# M705D.net
KiCad netlist of a schematic drawn in EAGLE
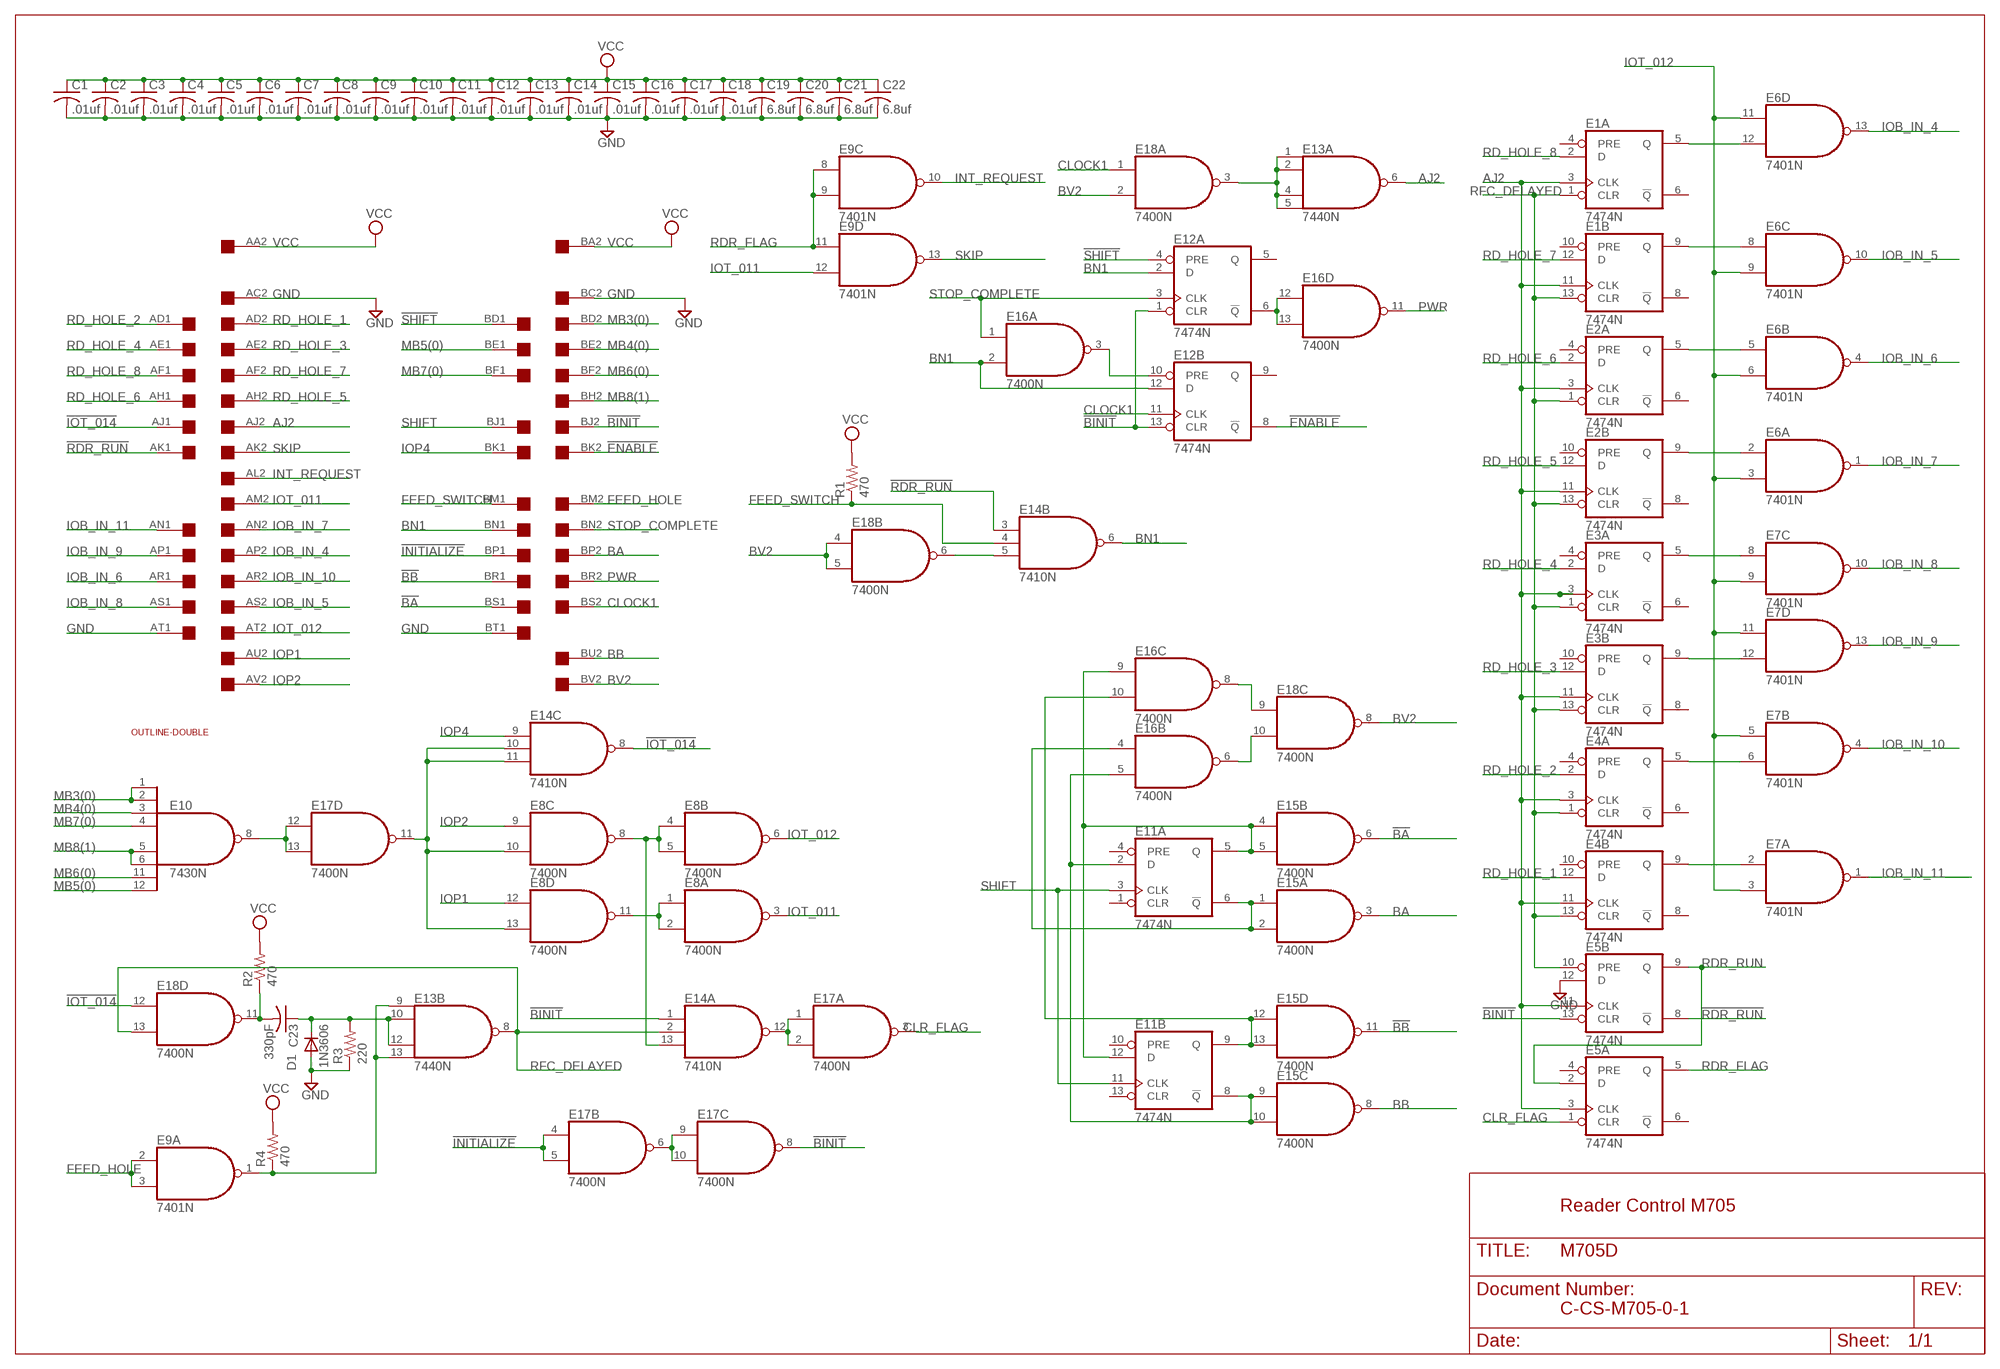
[diagram p0: schematic, sheet 1]

(export (version "E")
  (design (tool "Eeschema 10.0.6"))
  (components
    (comp (ref "C1")
      (value ".01uf")
      (footprint "eagle-import:C075-032X103")
      (libsource (lib "eagle-import") (part "C-US075-032X103"))
    )
    (comp (ref "C2")
      (value ".01uf")
      (footprint "eagle-import:C075-032X103")
      (libsource (lib "eagle-import") (part "C-US075-032X103"))
    )
    (comp (ref "C3")
      (value ".01uf")
      (footprint "eagle-import:C075-032X103")
      (libsource (lib "eagle-import") (part "C-US075-032X103"))
    )
    (comp (ref "C4")
      (value ".01uf")
      (footprint "eagle-import:C075-032X103")
      (libsource (lib "eagle-import") (part "C-US075-032X103"))
    )
    (comp (ref "C5")
      (value ".01uf")
      (footprint "eagle-import:C075-032X103")
      (libsource (lib "eagle-import") (part "C-US075-032X103"))
    )
    (comp (ref "C6")
      (value ".01uf")
      (footprint "eagle-import:C075-032X103")
      (libsource (lib "eagle-import") (part "C-US075-032X103"))
    )
    (comp (ref "C7")
      (value ".01uf")
      (footprint "eagle-import:C075-032X103")
      (libsource (lib "eagle-import") (part "C-US075-032X103"))
    )
    (comp (ref "C8")
      (value ".01uf")
      (footprint "eagle-import:C075-032X103")
      (libsource (lib "eagle-import") (part "C-US075-032X103"))
    )
    (comp (ref "C9")
      (value ".01uf")
      (footprint "eagle-import:C075-032X103")
      (libsource (lib "eagle-import") (part "C-US075-032X103"))
    )
    (comp (ref "C10")
      (value ".01uf")
      (footprint "eagle-import:C075-032X103")
      (libsource (lib "eagle-import") (part "C-US075-032X103"))
    )
    (comp (ref "C11")
      (value ".01uf")
      (footprint "eagle-import:C075-032X103")
      (libsource (lib "eagle-import") (part "C-US075-032X103"))
    )
    (comp (ref "C12")
      (value ".01uf")
      (footprint "eagle-import:C075-032X103")
      (libsource (lib "eagle-import") (part "C-US075-032X103"))
    )
    (comp (ref "C13")
      (value ".01uf")
      (footprint "eagle-import:C075-032X103")
      (libsource (lib "eagle-import") (part "C-US075-032X103"))
    )
    (comp (ref "C14")
      (value ".01uf")
      (footprint "eagle-import:C075-032X103")
      (libsource (lib "eagle-import") (part "C-US075-032X103"))
    )
    (comp (ref "C15")
      (value ".01uf")
      (footprint "eagle-import:C075-032X103")
      (libsource (lib "eagle-import") (part "C-US075-032X103"))
    )
    (comp (ref "C16")
      (value ".01uf")
      (footprint "eagle-import:C075-032X103")
      (libsource (lib "eagle-import") (part "C-US075-032X103"))
    )
    (comp (ref "C17")
      (value ".01uf")
      (footprint "eagle-import:C075-032X103")
      (libsource (lib "eagle-import") (part "C-US075-032X103"))
    )
    (comp (ref "C18")
      (value ".01uf")
      (footprint "eagle-import:C075-032X103")
      (libsource (lib "eagle-import") (part "C-US075-032X103"))
    )
    (comp (ref "C19")
      (value "6.8uf")
      (footprint "eagle-import:C150-054X183")
      (libsource (lib "eagle-import") (part "C-US150-054X183"))
    )
    (comp (ref "C20")
      (value "6.8uf")
      (footprint "eagle-import:C150-054X183")
      (libsource (lib "eagle-import") (part "C-US150-054X183"))
    )
    (comp (ref "C21")
      (value "6.8uf")
      (footprint "eagle-import:C150-054X183")
      (libsource (lib "eagle-import") (part "C-US150-054X183"))
    )
    (comp (ref "C22")
      (value "6.8uf")
      (footprint "eagle-import:C150-054X183")
      (libsource (lib "eagle-import") (part "C-US150-054X183"))
    )
    (comp (ref "C23")
      (value "330pF")
      (footprint "eagle-import:C075-032X103")
      (libsource (lib "eagle-import") (part "C-US075-032X103"))
    )
    (comp (ref "D1")
      (value "1N3606")
      (footprint "eagle-import:DO35-10")
      (libsource (lib "eagle-import") (part "1N4148DO35-10"))
    )
    (comp (ref "E1")
      (value "7474N")
      (footprint "eagle-import:DIL14")
      (libsource (lib "eagle-import") (part "7474NS"))
    )
    (comp (ref "E2")
      (value "7474N")
      (footprint "eagle-import:DIL14")
      (libsource (lib "eagle-import") (part "7474NS"))
    )
    (comp (ref "E3")
      (value "7474N")
      (footprint "eagle-import:DIL14")
      (libsource (lib "eagle-import") (part "7474NS"))
    )
    (comp (ref "E4")
      (value "7474N")
      (footprint "eagle-import:DIL14")
      (libsource (lib "eagle-import") (part "7474NS"))
    )
    (comp (ref "E5")
      (value "7474N")
      (footprint "eagle-import:DIL14")
      (libsource (lib "eagle-import") (part "7474NS"))
    )
    (comp (ref "E6")
      (value "7401N")
      (footprint "eagle-import:DIL14")
      (libsource (lib "eagle-import") (part "7401NLS"))
    )
    (comp (ref "E7")
      (value "7401N")
      (footprint "eagle-import:DIL14")
      (libsource (lib "eagle-import") (part "7401NLS"))
    )
    (comp (ref "E8")
      (value "7400N")
      (footprint "eagle-import:DIL14")
      (libsource (lib "eagle-import") (part "7400N"))
    )
    (comp (ref "E9")
      (value "7401N")
      (footprint "eagle-import:DIL14")
      (libsource (lib "eagle-import") (part "7401NLS"))
    )
    (comp (ref "E10")
      (value "7430N")
      (footprint "eagle-import:DIL14")
      (libsource (lib "eagle-import") (part "7430N"))
    )
    (comp (ref "E11")
      (value "7474N")
      (footprint "eagle-import:DIL14")
      (libsource (lib "eagle-import") (part "7474NS"))
    )
    (comp (ref "E12")
      (value "7474N")
      (footprint "eagle-import:DIL14")
      (libsource (lib "eagle-import") (part "7474NS"))
    )
    (comp (ref "E13")
      (value "7440N")
      (footprint "eagle-import:DIL14")
      (libsource (lib "eagle-import") (part "7420NS"))
    )
    (comp (ref "E14")
      (value "7410N")
      (footprint "eagle-import:DIL14")
      (libsource (lib "eagle-import") (part "7410N"))
    )
    (comp (ref "E15")
      (value "7400N")
      (footprint "eagle-import:DIL14")
      (libsource (lib "eagle-import") (part "7400N"))
    )
    (comp (ref "E16")
      (value "7400N")
      (footprint "eagle-import:DIL14")
      (libsource (lib "eagle-import") (part "7400N"))
    )
    (comp (ref "E17")
      (value "7400N")
      (footprint "eagle-import:DIL14")
      (libsource (lib "eagle-import") (part "7400N"))
    )
    (comp (ref "E18")
      (value "7400N")
      (footprint "eagle-import:DIL14")
      (libsource (lib "eagle-import") (part "7400N"))
    )
    (comp (ref "R1")
      (value "470")
      (footprint "eagle-import:0207_10")
      (libsource (lib "eagle-import") (part "R-US_0207/10"))
    )
    (comp (ref "R2")
      (value "470")
      (footprint "eagle-import:0207_10")
      (libsource (lib "eagle-import") (part "R-US_0207/10"))
    )
    (comp (ref "R3")
      (value "220")
      (footprint "eagle-import:0207_10")
      (libsource (lib "eagle-import") (part "R-US_0207/10"))
    )
    (comp (ref "R4")
      (value "470")
      (footprint "eagle-import:0207_10")
      (libsource (lib "eagle-import") (part "R-US_0207/10"))
    )
    (comp (ref "U$5")
      (value "DOUBLE")
      (footprint "eagle-import:EDGE-CON4")
      (libsource (lib "eagle-import") (part "DOUBLE"))
    )
    (comp (ref "U$6")
      (value "OUTLINE-DOUBLE")
      (footprint "eagle-import:DOUBLE")
      (libsource (lib "eagle-import") (part "OUTLINE-DOUBLE"))
    )
  )
  (nets
    (net (code "1") (name "/AJ2") (class "Default")
      (node (ref "E1") (pin "11") (pinfunction "CLK_11") (pintype "input"))
      (node (ref "E1") (pin "3") (pinfunction "CLK_3") (pintype "input"))
      (node (ref "E13") (pin "6") (pinfunction "O_6") (pintype "output"))
      (node (ref "E2") (pin "11") (pinfunction "CLK_11") (pintype "input"))
      (node (ref "E2") (pin "3") (pinfunction "CLK_3") (pintype "input"))
      (node (ref "E3") (pin "11") (pinfunction "CLK_11") (pintype "input"))
      (node (ref "E3") (pin "3") (pinfunction "CLK_3") (pintype "input"))
      (node (ref "E4") (pin "11") (pinfunction "CLK_11") (pintype "input"))
      (node (ref "E4") (pin "3") (pinfunction "CLK_3") (pintype "input"))
      (node (ref "E5") (pin "11") (pinfunction "CLK_11") (pintype "input"))
      (node (ref "E5") (pin "3") (pinfunction "CLK_3") (pintype "input"))
      (node (ref "U$5") (pin "AJ2") (pinfunction "1_AJ2") (pintype "bidirectional"))
    )
    (net (code "2") (name "/BA") (class "Default")
      (node (ref "E15") (pin "3") (pinfunction "O_3") (pintype "output"))
      (node (ref "U$5") (pin "BP2") (pinfunction "1_BP2") (pintype "bidirectional"))
    )
    (net (code "3") (name "/BB") (class "Default")
      (node (ref "E15") (pin "8") (pinfunction "O_8") (pintype "output"))
      (node (ref "U$5") (pin "BU2") (pinfunction "1_BU2") (pintype "bidirectional"))
    )
    (net (code "4") (name "/BN1") (class "Default")
      (node (ref "E12") (pin "12") (pinfunction "D_12") (pintype "input"))
      (node (ref "E12") (pin "2") (pinfunction "D_2") (pintype "input"))
      (node (ref "E14") (pin "6") (pinfunction "O_6") (pintype "output"))
      (node (ref "E16") (pin "2") (pinfunction "I1_2") (pintype "input"))
      (node (ref "U$5") (pin "BN1") (pinfunction "1_BN1") (pintype "bidirectional"))
    )
    (net (code "5") (name "/BV2") (class "Default")
      (node (ref "E18") (pin "2") (pinfunction "I1_2") (pintype "input"))
      (node (ref "E18") (pin "4") (pinfunction "I0_4") (pintype "input"))
      (node (ref "E18") (pin "5") (pinfunction "I1_5") (pintype "input"))
      (node (ref "E18") (pin "8") (pinfunction "O_8") (pintype "output"))
      (node (ref "U$5") (pin "BV2") (pinfunction "1_BV2") (pintype "bidirectional"))
    )
    (net (code "6") (name "/CLOCK1") (class "Default")
      (node (ref "E12") (pin "11") (pinfunction "CLK_11") (pintype "input"))
      (node (ref "E18") (pin "1") (pinfunction "I0_1") (pintype "input"))
      (node (ref "U$5") (pin "BS2") (pinfunction "1_BS2") (pintype "bidirectional"))
    )
    (net (code "7") (name "/CLR_FLAG") (class "Default")
      (node (ref "E17") (pin "3") (pinfunction "O_3") (pintype "output"))
      (node (ref "E5") (pin "1") (pinfunction "CLR_1") (pintype "input"))
    )
    (net (code "8") (name "/FEED_HOLE") (class "Default")
      (node (ref "E9") (pin "2") (pinfunction "I0_2") (pintype "input"))
      (node (ref "E9") (pin "3") (pinfunction "I1_3") (pintype "input"))
      (node (ref "U$5") (pin "BM2") (pinfunction "1_BM2") (pintype "bidirectional"))
    )
    (net (code "9") (name "/FEED_SWITCH") (class "Default")
      (node (ref "E14") (pin "4") (pinfunction "I1_4") (pintype "input"))
      (node (ref "R1") (pin "1") (pinfunction "1_1") (pintype "passive"))
      (node (ref "U$5") (pin "BM1") (pinfunction "1_BM1") (pintype "bidirectional"))
    )
    (net (code "10") (name "/INT_REQUEST") (class "Default")
      (node (ref "E9") (pin "10") (pinfunction "O_10") (pintype "open_collector"))
      (node (ref "U$5") (pin "AL2") (pinfunction "1_AL2") (pintype "bidirectional"))
    )
    (net (code "11") (name "/IOB_IN_4") (class "Default")
      (node (ref "E6") (pin "13") (pinfunction "O_13") (pintype "open_collector"))
      (node (ref "U$5") (pin "AP2") (pinfunction "1_AP2") (pintype "bidirectional"))
    )
    (net (code "12") (name "/IOB_IN_5") (class "Default")
      (node (ref "E6") (pin "10") (pinfunction "O_10") (pintype "open_collector"))
      (node (ref "U$5") (pin "AS2") (pinfunction "1_AS2") (pintype "bidirectional"))
    )
    (net (code "13") (name "/IOB_IN_6") (class "Default")
      (node (ref "E6") (pin "4") (pinfunction "O_4") (pintype "open_collector"))
      (node (ref "U$5") (pin "AR1") (pinfunction "1_AR1") (pintype "bidirectional"))
    )
    (net (code "14") (name "/IOB_IN_7") (class "Default")
      (node (ref "E6") (pin "1") (pinfunction "O_1") (pintype "open_collector"))
      (node (ref "U$5") (pin "AN2") (pinfunction "1_AN2") (pintype "bidirectional"))
    )
    (net (code "15") (name "/IOB_IN_8") (class "Default")
      (node (ref "E7") (pin "10") (pinfunction "O_10") (pintype "open_collector"))
      (node (ref "U$5") (pin "AS1") (pinfunction "1_AS1") (pintype "bidirectional"))
    )
    (net (code "16") (name "/IOB_IN_9") (class "Default")
      (node (ref "E7") (pin "13") (pinfunction "O_13") (pintype "open_collector"))
      (node (ref "U$5") (pin "AP1") (pinfunction "1_AP1") (pintype "bidirectional"))
    )
    (net (code "17") (name "/IOB_IN_10") (class "Default")
      (node (ref "E7") (pin "4") (pinfunction "O_4") (pintype "open_collector"))
      (node (ref "U$5") (pin "AR2") (pinfunction "1_AR2") (pintype "bidirectional"))
    )
    (net (code "18") (name "/IOB_IN_11") (class "Default")
      (node (ref "E7") (pin "1") (pinfunction "O_1") (pintype "open_collector"))
      (node (ref "U$5") (pin "AN1") (pinfunction "1_AN1") (pintype "bidirectional"))
    )
    (net (code "19") (name "/IOP1") (class "Default")
      (node (ref "E8") (pin "12") (pinfunction "I0_12") (pintype "input"))
      (node (ref "U$5") (pin "AU2") (pinfunction "1_AU2") (pintype "bidirectional"))
    )
    (net (code "20") (name "/IOP2") (class "Default")
      (node (ref "E8") (pin "9") (pinfunction "I0_9") (pintype "input"))
      (node (ref "U$5") (pin "AV2") (pinfunction "1_AV2") (pintype "bidirectional"))
    )
    (net (code "21") (name "/IOP4") (class "Default")
      (node (ref "E14") (pin "9") (pinfunction "I0_9") (pintype "input"))
      (node (ref "U$5") (pin "BK1") (pinfunction "1_BK1") (pintype "bidirectional"))
    )
    (net (code "22") (name "/IOT_011") (class "Default")
      (node (ref "E8") (pin "3") (pinfunction "O_3") (pintype "output"))
      (node (ref "E9") (pin "12") (pinfunction "I1_12") (pintype "input"))
      (node (ref "U$5") (pin "AM2") (pinfunction "1_AM2") (pintype "bidirectional"))
    )
    (net (code "23") (name "/IOT_012") (class "Default")
      (node (ref "E6") (pin "11") (pinfunction "I0_11") (pintype "input"))
      (node (ref "E6") (pin "3") (pinfunction "I1_3") (pintype "input"))
      (node (ref "E6") (pin "6") (pinfunction "I1_6") (pintype "input"))
      (node (ref "E6") (pin "9") (pinfunction "I1_9") (pintype "input"))
      (node (ref "E7") (pin "11") (pinfunction "I0_11") (pintype "input"))
      (node (ref "E7") (pin "3") (pinfunction "I1_3") (pintype "input"))
      (node (ref "E7") (pin "5") (pinfunction "I0_5") (pintype "input"))
      (node (ref "E7") (pin "9") (pinfunction "I1_9") (pintype "input"))
      (node (ref "E8") (pin "6") (pinfunction "O_6") (pintype "output"))
      (node (ref "U$5") (pin "AT2") (pinfunction "1_AT2") (pintype "bidirectional"))
    )
    (net (code "24") (name "/MB3(0)") (class "Default")
      (node (ref "E10") (pin "1") (pinfunction "I0_1") (pintype "input"))
      (node (ref "E10") (pin "2") (pinfunction "I1_2") (pintype "input"))
      (node (ref "U$5") (pin "BD2") (pinfunction "1_BD2") (pintype "bidirectional"))
    )
    (net (code "25") (name "/MB4(0)") (class "Default")
      (node (ref "E10") (pin "3") (pinfunction "I2_3") (pintype "input"))
      (node (ref "U$5") (pin "BE2") (pinfunction "1_BE2") (pintype "bidirectional"))
    )
    (net (code "26") (name "/MB5(0)") (class "Default")
      (node (ref "E10") (pin "12") (pinfunction "I7_12") (pintype "input"))
      (node (ref "U$5") (pin "BE1") (pinfunction "1_BE1") (pintype "bidirectional"))
    )
    (net (code "27") (name "/MB6(0)") (class "Default")
      (node (ref "E10") (pin "11") (pinfunction "I6_11") (pintype "input"))
      (node (ref "U$5") (pin "BF2") (pinfunction "1_BF2") (pintype "bidirectional"))
    )
    (net (code "28") (name "/MB7(0)") (class "Default")
      (node (ref "E10") (pin "4") (pinfunction "I3_4") (pintype "input"))
      (node (ref "U$5") (pin "BF1") (pinfunction "1_BF1") (pintype "bidirectional"))
    )
    (net (code "29") (name "/MB8(1)") (class "Default")
      (node (ref "E10") (pin "5") (pinfunction "I4_5") (pintype "input"))
      (node (ref "E10") (pin "6") (pinfunction "I5_6") (pintype "input"))
      (node (ref "U$5") (pin "BH2") (pinfunction "1_BH2") (pintype "bidirectional"))
    )
    (net (code "30") (name "/PWR") (class "Default")
      (node (ref "E16") (pin "11") (pinfunction "O_11") (pintype "output"))
      (node (ref "U$5") (pin "BR2") (pinfunction "1_BR2") (pintype "bidirectional"))
    )
    (net (code "31") (name "/RDR_FLAG") (class "Default")
      (node (ref "E5") (pin "5") (pinfunction "Q_5") (pintype "output"))
      (node (ref "E9") (pin "11") (pinfunction "I0_11") (pintype "input"))
      (node (ref "E9") (pin "8") (pinfunction "I0_8") (pintype "input"))
      (node (ref "E9") (pin "9") (pinfunction "I1_9") (pintype "input"))
    )
    (net (code "32") (name "/RDR_RUN") (class "Default")
      (node (ref "E5") (pin "2") (pinfunction "D_2") (pintype "input"))
      (node (ref "E5") (pin "9") (pinfunction "Q_9") (pintype "output"))
    )
    (net (code "33") (name "/RD_HOLE_1") (class "Default")
      (node (ref "E4") (pin "12") (pinfunction "D_12") (pintype "input"))
      (node (ref "U$5") (pin "AD2") (pinfunction "1_AD2") (pintype "bidirectional"))
    )
    (net (code "34") (name "/RD_HOLE_2") (class "Default")
      (node (ref "E4") (pin "2") (pinfunction "D_2") (pintype "input"))
      (node (ref "U$5") (pin "AD1") (pinfunction "1_AD1") (pintype "bidirectional"))
    )
    (net (code "35") (name "/RD_HOLE_3") (class "Default")
      (node (ref "E3") (pin "12") (pinfunction "D_12") (pintype "input"))
      (node (ref "U$5") (pin "AE2") (pinfunction "1_AE2") (pintype "bidirectional"))
    )
    (net (code "36") (name "/RD_HOLE_4") (class "Default")
      (node (ref "E3") (pin "2") (pinfunction "D_2") (pintype "input"))
      (node (ref "U$5") (pin "AE1") (pinfunction "1_AE1") (pintype "bidirectional"))
    )
    (net (code "37") (name "/RD_HOLE_5") (class "Default")
      (node (ref "E2") (pin "12") (pinfunction "D_12") (pintype "input"))
      (node (ref "U$5") (pin "AH2") (pinfunction "1_AH2") (pintype "bidirectional"))
    )
    (net (code "38") (name "/RD_HOLE_6") (class "Default")
      (node (ref "E2") (pin "2") (pinfunction "D_2") (pintype "input"))
      (node (ref "U$5") (pin "AH1") (pinfunction "1_AH1") (pintype "bidirectional"))
    )
    (net (code "39") (name "/RD_HOLE_7") (class "Default")
      (node (ref "E1") (pin "12") (pinfunction "D_12") (pintype "input"))
      (node (ref "U$5") (pin "AF2") (pinfunction "1_AF2") (pintype "bidirectional"))
    )
    (net (code "40") (name "/RD_HOLE_8") (class "Default")
      (node (ref "E1") (pin "2") (pinfunction "D_2") (pintype "input"))
      (node (ref "U$5") (pin "AF1") (pinfunction "1_AF1") (pintype "bidirectional"))
    )
    (net (code "41") (name "/RFC_DELAYED") (class "Default")
      (node (ref "E1") (pin "1") (pinfunction "CLR_1") (pintype "input"))
      (node (ref "E1") (pin "13") (pinfunction "CLR_13") (pintype "input"))
      (node (ref "E13") (pin "8") (pinfunction "O_8") (pintype "output"))
      (node (ref "E14") (pin "2") (pinfunction "I1_2") (pintype "input"))
      (node (ref "E18") (pin "13") (pinfunction "I1_13") (pintype "input"))
      (node (ref "E2") (pin "1") (pinfunction "CLR_1") (pintype "input"))
      (node (ref "E2") (pin "13") (pinfunction "CLR_13") (pintype "input"))
      (node (ref "E3") (pin "1") (pinfunction "CLR_1") (pintype "input"))
      (node (ref "E3") (pin "13") (pinfunction "CLR_13") (pintype "input"))
      (node (ref "E4") (pin "1") (pinfunction "CLR_1") (pintype "input"))
      (node (ref "E4") (pin "13") (pinfunction "CLR_13") (pintype "input"))
      (node (ref "E5") (pin "10") (pinfunction "PRE_10") (pintype "input"))
    )
    (net (code "42") (name "/SHIFT") (class "Default")
      (node (ref "E11") (pin "11") (pinfunction "CLK_11") (pintype "input"))
      (node (ref "E11") (pin "3") (pinfunction "CLK_3") (pintype "input"))
      (node (ref "U$5") (pin "BJ1") (pinfunction "1_BJ1") (pintype "bidirectional"))
    )
    (net (code "43") (name "/SKIP") (class "Default")
      (node (ref "E9") (pin "13") (pinfunction "O_13") (pintype "open_collector"))
      (node (ref "U$5") (pin "AK2") (pinfunction "1_AK2") (pintype "bidirectional"))
    )
    (net (code "44") (name "/STOP_COMPLETE") (class "Default")
      (node (ref "E12") (pin "3") (pinfunction "CLK_3") (pintype "input"))
      (node (ref "E16") (pin "1") (pinfunction "I0_1") (pintype "input"))
      (node (ref "U$5") (pin "BN2") (pinfunction "1_BN2") (pintype "bidirectional"))
    )
    (net (code "45") (name "/~{BA}") (class "Default")
      (node (ref "E15") (pin "6") (pinfunction "O_6") (pintype "output"))
      (node (ref "U$5") (pin "BS1") (pinfunction "1_BS1") (pintype "bidirectional"))
    )
    (net (code "46") (name "/~{BB}") (class "Default")
      (node (ref "E15") (pin "11") (pinfunction "O_11") (pintype "output"))
      (node (ref "U$5") (pin "BR1") (pinfunction "1_BR1") (pintype "bidirectional"))
    )
    (net (code "47") (name "/~{BINIT}") (class "Default")
      (node (ref "E12") (pin "1") (pinfunction "CLR_1") (pintype "input"))
      (node (ref "E12") (pin "13") (pinfunction "CLR_13") (pintype "input"))
      (node (ref "E14") (pin "1") (pinfunction "I0_1") (pintype "input"))
      (node (ref "E17") (pin "8") (pinfunction "O_8") (pintype "output"))
      (node (ref "E5") (pin "13") (pinfunction "CLR_13") (pintype "input"))
      (node (ref "U$5") (pin "BJ2") (pinfunction "1_BJ2") (pintype "bidirectional"))
    )
    (net (code "48") (name "/~{ENABLE}") (class "Default")
      (node (ref "E12") (pin "8") (pinfunction "~{Q}_8") (pintype "output"))
      (node (ref "U$5") (pin "BK2") (pinfunction "1_BK2") (pintype "bidirectional"))
    )
    (net (code "49") (name "/~{INITIALIZE}") (class "Default")
      (node (ref "E17") (pin "4") (pinfunction "I0_4") (pintype "input"))
      (node (ref "E17") (pin "5") (pinfunction "I1_5") (pintype "input"))
      (node (ref "U$5") (pin "BP1") (pinfunction "1_BP1") (pintype "bidirectional"))
    )
    (net (code "50") (name "/~{IOT_014}") (class "Default")
      (node (ref "E14") (pin "8") (pinfunction "O_8") (pintype "output"))
      (node (ref "E18") (pin "12") (pinfunction "I0_12") (pintype "input"))
      (node (ref "U$5") (pin "AJ1") (pinfunction "1_AJ1") (pintype "bidirectional"))
    )
    (net (code "51") (name "/~{RDR_RUN}") (class "Default")
      (node (ref "E14") (pin "3") (pinfunction "I0_3") (pintype "input"))
      (node (ref "E5") (pin "8") (pinfunction "~{Q}_8") (pintype "output"))
      (node (ref "U$5") (pin "AK1") (pinfunction "1_AK1") (pintype "bidirectional"))
    )
    (net (code "52") (name "/~{SHIFT}") (class "Default")
      (node (ref "E12") (pin "4") (pinfunction "PRE_4") (pintype "input"))
      (node (ref "U$5") (pin "BD1") (pinfunction "1_BD1") (pintype "bidirectional"))
    )
    (net (code "53") (name "GND") (class "Default")
      (node (ref "C1") (pin "2") (pinfunction "2_2") (pintype "passive"))
      (node (ref "C10") (pin "2") (pinfunction "2_2") (pintype "passive"))
      (node (ref "C11") (pin "2") (pinfunction "2_2") (pintype "passive"))
      (node (ref "C12") (pin "2") (pinfunction "2_2") (pintype "passive"))
      (node (ref "C13") (pin "2") (pinfunction "2_2") (pintype "passive"))
      (node (ref "C14") (pin "2") (pinfunction "2_2") (pintype "passive"))
      (node (ref "C15") (pin "2") (pinfunction "2_2") (pintype "passive"))
      (node (ref "C16") (pin "2") (pinfunction "2_2") (pintype "passive"))
      (node (ref "C17") (pin "2") (pinfunction "2_2") (pintype "passive"))
      (node (ref "C18") (pin "2") (pinfunction "2_2") (pintype "passive"))
      (node (ref "C19") (pin "2") (pinfunction "2_2") (pintype "passive"))
      (node (ref "C2") (pin "2") (pinfunction "2_2") (pintype "passive"))
      (node (ref "C20") (pin "2") (pinfunction "2_2") (pintype "passive"))
      (node (ref "C21") (pin "2") (pinfunction "2_2") (pintype "passive"))
      (node (ref "C22") (pin "2") (pinfunction "2_2") (pintype "passive"))
      (node (ref "C3") (pin "2") (pinfunction "2_2") (pintype "passive"))
      (node (ref "C4") (pin "2") (pinfunction "2_2") (pintype "passive"))
      (node (ref "C5") (pin "2") (pinfunction "2_2") (pintype "passive"))
      (node (ref "C6") (pin "2") (pinfunction "2_2") (pintype "passive"))
      (node (ref "C7") (pin "2") (pinfunction "2_2") (pintype "passive"))
      (node (ref "C8") (pin "2") (pinfunction "2_2") (pintype "passive"))
      (node (ref "C9") (pin "2") (pinfunction "2_2") (pintype "passive"))
      (node (ref "D1") (pin "A") (pinfunction "A_A") (pintype "passive"))
      (node (ref "E5") (pin "12") (pinfunction "D_12") (pintype "input"))
      (node (ref "R3") (pin "1") (pinfunction "1_1") (pintype "passive"))
      (node (ref "U$5") (pin "AC2") (pinfunction "1_AC2") (pintype "bidirectional"))
      (node (ref "U$5") (pin "AT1") (pinfunction "1_AT1") (pintype "bidirectional"))
      (node (ref "U$5") (pin "BC2") (pinfunction "1_BC2") (pintype "bidirectional"))
      (node (ref "U$5") (pin "BT1") (pinfunction "1_BT1") (pintype "bidirectional"))
    )
    (net (code "54") (name "Net-(E1A-Q)") (class "Default")
      (node (ref "E1") (pin "5") (pinfunction "Q_5") (pintype "output"))
      (node (ref "E6") (pin "12") (pinfunction "I1_12") (pintype "input"))
    )
    (net (code "55") (name "Net-(E1B-Q)") (class "Default")
      (node (ref "E1") (pin "9") (pinfunction "Q_9") (pintype "output"))
      (node (ref "E6") (pin "8") (pinfunction "I0_8") (pintype "input"))
    )
    (net (code "56") (name "Net-(E2A-Q)") (class "Default")
      (node (ref "E2") (pin "5") (pinfunction "Q_5") (pintype "output"))
      (node (ref "E6") (pin "5") (pinfunction "I0_5") (pintype "input"))
    )
    (net (code "57") (name "Net-(E2B-Q)") (class "Default")
      (node (ref "E2") (pin "9") (pinfunction "Q_9") (pintype "output"))
      (node (ref "E6") (pin "2") (pinfunction "I0_2") (pintype "input"))
    )
    (net (code "58") (name "Net-(E3A-Q)") (class "Default")
      (node (ref "E3") (pin "5") (pinfunction "Q_5") (pintype "output"))
      (node (ref "E7") (pin "8") (pinfunction "I0_8") (pintype "input"))
    )
    (net (code "59") (name "Net-(E3B-Q)") (class "Default")
      (node (ref "E3") (pin "9") (pinfunction "Q_9") (pintype "output"))
      (node (ref "E7") (pin "12") (pinfunction "I1_12") (pintype "input"))
    )
    (net (code "60") (name "Net-(E4A-Q)") (class "Default")
      (node (ref "E4") (pin "5") (pinfunction "Q_5") (pintype "output"))
      (node (ref "E7") (pin "6") (pinfunction "I1_6") (pintype "input"))
    )
    (net (code "61") (name "Net-(E4B-Q)") (class "Default")
      (node (ref "E4") (pin "9") (pinfunction "Q_9") (pintype "output"))
      (node (ref "E7") (pin "2") (pinfunction "I0_2") (pintype "input"))
    )
    (net (code "62") (name "Net-(E8A-I0)") (class "Default")
      (node (ref "E8") (pin "1") (pinfunction "I0_1") (pintype "input"))
      (node (ref "E8") (pin "11") (pinfunction "O_11") (pintype "output"))
      (node (ref "E8") (pin "2") (pinfunction "I1_2") (pintype "input"))
    )
    (net (code "63") (name "Net-(E10A-O)") (class "Default")
      (node (ref "E10") (pin "8") (pinfunction "O_8") (pintype "output"))
      (node (ref "E17") (pin "12") (pinfunction "I0_12") (pintype "input"))
      (node (ref "E17") (pin "13") (pinfunction "I1_13") (pintype "input"))
    )
    (net (code "64") (name "Net-(E11A-D)") (class "Default")
      (node (ref "E11") (pin "2") (pinfunction "D_2") (pintype "input"))
      (node (ref "E11") (pin "8") (pinfunction "~{Q}_8") (pintype "output"))
      (node (ref "E15") (pin "10") (pinfunction "I1_10") (pintype "input"))
      (node (ref "E15") (pin "9") (pinfunction "I0_9") (pintype "input"))
      (node (ref "E16") (pin "5") (pinfunction "I1_5") (pintype "input"))
    )
    (net (code "65") (name "Net-(E11A-Q)") (class "Default")
      (node (ref "E11") (pin "12") (pinfunction "D_12") (pintype "input"))
      (node (ref "E11") (pin "5") (pinfunction "Q_5") (pintype "output"))
      (node (ref "E15") (pin "4") (pinfunction "I0_4") (pintype "input"))
      (node (ref "E15") (pin "5") (pinfunction "I1_5") (pintype "input"))
      (node (ref "E16") (pin "9") (pinfunction "I0_9") (pintype "input"))
    )
    (net (code "66") (name "Net-(E11A-~{Q})") (class "Default")
      (node (ref "E11") (pin "6") (pinfunction "~{Q}_6") (pintype "output"))
      (node (ref "E15") (pin "1") (pinfunction "I0_1") (pintype "input"))
      (node (ref "E15") (pin "2") (pinfunction "I1_2") (pintype "input"))
      (node (ref "E16") (pin "4") (pinfunction "I0_4") (pintype "input"))
    )
    (net (code "67") (name "Net-(E11B-Q)") (class "Default")
      (node (ref "E11") (pin "9") (pinfunction "Q_9") (pintype "output"))
      (node (ref "E15") (pin "12") (pinfunction "I0_12") (pintype "input"))
      (node (ref "E15") (pin "13") (pinfunction "I1_13") (pintype "input"))
      (node (ref "E16") (pin "10") (pinfunction "I1_10") (pintype "input"))
    )
    (net (code "68") (name "Net-(E12A-~{Q})") (class "Default")
      (node (ref "E12") (pin "6") (pinfunction "~{Q}_6") (pintype "output"))
      (node (ref "E16") (pin "12") (pinfunction "I0_12") (pintype "input"))
      (node (ref "E16") (pin "13") (pinfunction "I1_13") (pintype "input"))
    )
    (net (code "69") (name "Net-(E12B-PRE)") (class "Default")
      (node (ref "E12") (pin "10") (pinfunction "PRE_10") (pintype "input"))
      (node (ref "E16") (pin "3") (pinfunction "O_3") (pintype "output"))
    )
    (net (code "70") (name "Net-(E13A-I0)") (class "Default")
      (node (ref "E13") (pin "1") (pinfunction "I0_1") (pintype "input"))
      (node (ref "E13") (pin "2") (pinfunction "I1_2") (pintype "input"))
      (node (ref "E13") (pin "4") (pinfunction "I2_4") (pintype "input"))
      (node (ref "E13") (pin "5") (pinfunction "I3_5") (pintype "input"))
      (node (ref "E18") (pin "3") (pinfunction "O_3") (pintype "output"))
    )
    (net (code "71") (name "Net-(E13B-I0)") (class "Default")
      (node (ref "E13") (pin "13") (pinfunction "I3_13") (pintype "input"))
      (node (ref "E13") (pin "9") (pinfunction "I0_9") (pintype "input"))
      (node (ref "E9") (pin "1") (pinfunction "O_1") (pintype "open_collector"))
      (node (ref "R4") (pin "1") (pinfunction "1_1") (pintype "passive"))
    )
    (net (code "72") (name "Net-(E13B-I1)") (class "Default")
      (node (ref "C23") (pin "1") (pinfunction "1_1") (pintype "passive"))
      (node (ref "D1") (pin "C") (pinfunction "C_C") (pintype "passive"))
      (node (ref "E13") (pin "10") (pinfunction "I1_10") (pintype "input"))
      (node (ref "E13") (pin "12") (pinfunction "I2_12") (pintype "input"))
      (node (ref "R3") (pin "2") (pinfunction "2_2") (pintype "passive"))
    )
    (net (code "73") (name "Net-(E14A-I2)") (class "Default")
      (node (ref "E14") (pin "13") (pinfunction "I2_13") (pintype "input"))
      (node (ref "E8") (pin "4") (pinfunction "I0_4") (pintype "input"))
      (node (ref "E8") (pin "5") (pinfunction "I1_5") (pintype "input"))
      (node (ref "E8") (pin "8") (pinfunction "O_8") (pintype "output"))
    )
    (net (code "74") (name "Net-(E14A-O)") (class "Default")
      (node (ref "E14") (pin "12") (pinfunction "O_12") (pintype "output"))
      (node (ref "E17") (pin "1") (pinfunction "I0_1") (pintype "input"))
      (node (ref "E17") (pin "2") (pinfunction "I1_2") (pintype "input"))
    )
    (net (code "75") (name "Net-(E14B-I2)") (class "Default")
      (node (ref "E14") (pin "5") (pinfunction "I2_5") (pintype "input"))
      (node (ref "E18") (pin "6") (pinfunction "O_6") (pintype "output"))
    )
    (net (code "76") (name "Net-(E14C-I1)") (class "Default")
      (node (ref "E14") (pin "10") (pinfunction "I1_10") (pintype "input"))
      (node (ref "E14") (pin "11") (pinfunction "I2_11") (pintype "input"))
      (node (ref "E17") (pin "11") (pinfunction "O_11") (pintype "output"))
      (node (ref "E8") (pin "10") (pinfunction "I1_10") (pintype "input"))
      (node (ref "E8") (pin "13") (pinfunction "I1_13") (pintype "input"))
    )
    (net (code "77") (name "Net-(E16B-O)") (class "Default")
      (node (ref "E16") (pin "6") (pinfunction "O_6") (pintype "output"))
      (node (ref "E18") (pin "10") (pinfunction "I1_10") (pintype "input"))
    )
    (net (code "78") (name "Net-(E16C-O)") (class "Default")
      (node (ref "E16") (pin "8") (pinfunction "O_8") (pintype "output"))
      (node (ref "E18") (pin "9") (pinfunction "I0_9") (pintype "input"))
    )
    (net (code "79") (name "Net-(E17B-O)") (class "Default")
      (node (ref "E17") (pin "10") (pinfunction "I1_10") (pintype "input"))
      (node (ref "E17") (pin "6") (pinfunction "O_6") (pintype "output"))
      (node (ref "E17") (pin "9") (pinfunction "I0_9") (pintype "input"))
    )
    (net (code "80") (name "Net-(E18D-O)") (class "Default")
      (node (ref "C23") (pin "2") (pinfunction "2_2") (pintype "passive"))
      (node (ref "E18") (pin "11") (pinfunction "O_11") (pintype "output"))
      (node (ref "R2") (pin "1") (pinfunction "1_1") (pintype "passive"))
    )
    (net (code "81") (name "VCC") (class "Default")
      (node (ref "C1") (pin "1") (pinfunction "1_1") (pintype "passive"))
      (node (ref "C10") (pin "1") (pinfunction "1_1") (pintype "passive"))
      (node (ref "C11") (pin "1") (pinfunction "1_1") (pintype "passive"))
      (node (ref "C12") (pin "1") (pinfunction "1_1") (pintype "passive"))
      (node (ref "C13") (pin "1") (pinfunction "1_1") (pintype "passive"))
      (node (ref "C14") (pin "1") (pinfunction "1_1") (pintype "passive"))
      (node (ref "C15") (pin "1") (pinfunction "1_1") (pintype "passive"))
      (node (ref "C16") (pin "1") (pinfunction "1_1") (pintype "passive"))
      (node (ref "C17") (pin "1") (pinfunction "1_1") (pintype "passive"))
      (node (ref "C18") (pin "1") (pinfunction "1_1") (pintype "passive"))
      (node (ref "C19") (pin "1") (pinfunction "1_1") (pintype "passive"))
      (node (ref "C2") (pin "1") (pinfunction "1_1") (pintype "passive"))
      (node (ref "C20") (pin "1") (pinfunction "1_1") (pintype "passive"))
      (node (ref "C21") (pin "1") (pinfunction "1_1") (pintype "passive"))
      (node (ref "C22") (pin "1") (pinfunction "1_1") (pintype "passive"))
      (node (ref "C3") (pin "1") (pinfunction "1_1") (pintype "passive"))
      (node (ref "C4") (pin "1") (pinfunction "1_1") (pintype "passive"))
      (node (ref "C5") (pin "1") (pinfunction "1_1") (pintype "passive"))
      (node (ref "C6") (pin "1") (pinfunction "1_1") (pintype "passive"))
      (node (ref "C7") (pin "1") (pinfunction "1_1") (pintype "passive"))
      (node (ref "C8") (pin "1") (pinfunction "1_1") (pintype "passive"))
      (node (ref "C9") (pin "1") (pinfunction "1_1") (pintype "passive"))
      (node (ref "R1") (pin "2") (pinfunction "2_2") (pintype "passive"))
      (node (ref "R2") (pin "2") (pinfunction "2_2") (pintype "passive"))
      (node (ref "R4") (pin "2") (pinfunction "2_2") (pintype "passive"))
      (node (ref "U$5") (pin "AA2") (pinfunction "1_AA2") (pintype "bidirectional"))
      (node (ref "U$5") (pin "BA2") (pinfunction "1_BA2") (pintype "bidirectional"))
    )
    (net (code "82") (name "unconnected-(E1A-PRE-Pad4)") (class "Default")
      (node (ref "E1") (pin "4") (pinfunction "PRE_4") (pintype "input"))
    )
    (net (code "83") (name "unconnected-(E1A-~{Q}-Pad6)") (class "Default")
      (node (ref "E1") (pin "6") (pinfunction "~{Q}_6") (pintype "output"))
    )
    (net (code "84") (name "unconnected-(E1B-PRE-Pad10)") (class "Default")
      (node (ref "E1") (pin "10") (pinfunction "PRE_10") (pintype "input"))
    )
    (net (code "85") (name "unconnected-(E1B-~{Q}-Pad8)") (class "Default")
      (node (ref "E1") (pin "8") (pinfunction "~{Q}_8") (pintype "output"))
    )
    (net (code "86") (name "unconnected-(E2A-PRE-Pad4)") (class "Default")
      (node (ref "E2") (pin "4") (pinfunction "PRE_4") (pintype "input"))
    )
    (net (code "87") (name "unconnected-(E2A-~{Q}-Pad6)") (class "Default")
      (node (ref "E2") (pin "6") (pinfunction "~{Q}_6") (pintype "output"))
    )
    (net (code "88") (name "unconnected-(E2B-PRE-Pad10)") (class "Default")
      (node (ref "E2") (pin "10") (pinfunction "PRE_10") (pintype "input"))
    )
    (net (code "89") (name "unconnected-(E2B-~{Q}-Pad8)") (class "Default")
      (node (ref "E2") (pin "8") (pinfunction "~{Q}_8") (pintype "output"))
    )
    (net (code "90") (name "unconnected-(E3A-PRE-Pad4)") (class "Default")
      (node (ref "E3") (pin "4") (pinfunction "PRE_4") (pintype "input"))
    )
    (net (code "91") (name "unconnected-(E3A-~{Q}-Pad6)") (class "Default")
      (node (ref "E3") (pin "6") (pinfunction "~{Q}_6") (pintype "output"))
    )
    (net (code "92") (name "unconnected-(E3B-PRE-Pad10)") (class "Default")
      (node (ref "E3") (pin "10") (pinfunction "PRE_10") (pintype "input"))
    )
    (net (code "93") (name "unconnected-(E3B-~{Q}-Pad8)") (class "Default")
      (node (ref "E3") (pin "8") (pinfunction "~{Q}_8") (pintype "output"))
    )
    (net (code "94") (name "unconnected-(E4A-PRE-Pad4)") (class "Default")
      (node (ref "E4") (pin "4") (pinfunction "PRE_4") (pintype "input"))
    )
    (net (code "95") (name "unconnected-(E4A-~{Q}-Pad6)") (class "Default")
      (node (ref "E4") (pin "6") (pinfunction "~{Q}_6") (pintype "output"))
    )
    (net (code "96") (name "unconnected-(E4B-PRE-Pad10)") (class "Default")
      (node (ref "E4") (pin "10") (pinfunction "PRE_10") (pintype "input"))
    )
    (net (code "97") (name "unconnected-(E4B-~{Q}-Pad8)") (class "Default")
      (node (ref "E4") (pin "8") (pinfunction "~{Q}_8") (pintype "output"))
    )
    (net (code "98") (name "unconnected-(E5A-PRE-Pad4)") (class "Default")
      (node (ref "E5") (pin "4") (pinfunction "PRE_4") (pintype "input"))
    )
    (net (code "99") (name "unconnected-(E5A-~{Q}-Pad6)") (class "Default")
      (node (ref "E5") (pin "6") (pinfunction "~{Q}_6") (pintype "output"))
    )
    (net (code "100") (name "unconnected-(E11A-CLR-Pad1)") (class "Default")
      (node (ref "E11") (pin "1") (pinfunction "CLR_1") (pintype "input"))
    )
    (net (code "101") (name "unconnected-(E11A-PRE-Pad4)") (class "Default")
      (node (ref "E11") (pin "4") (pinfunction "PRE_4") (pintype "input"))
    )
    (net (code "102") (name "unconnected-(E11B-CLR-Pad13)") (class "Default")
      (node (ref "E11") (pin "13") (pinfunction "CLR_13") (pintype "input"))
    )
    (net (code "103") (name "unconnected-(E11B-PRE-Pad10)") (class "Default")
      (node (ref "E11") (pin "10") (pinfunction "PRE_10") (pintype "input"))
    )
    (net (code "104") (name "unconnected-(E12A-Q-Pad5)") (class "Default")
      (node (ref "E12") (pin "5") (pinfunction "Q_5") (pintype "output"))
    )
    (net (code "105") (name "unconnected-(E12B-Q-Pad9)") (class "Default")
      (node (ref "E12") (pin "9") (pinfunction "Q_9") (pintype "output"))
    )
  )
)
